# UART.net
KiCad netlist of a schematic drawn in Altium Designer
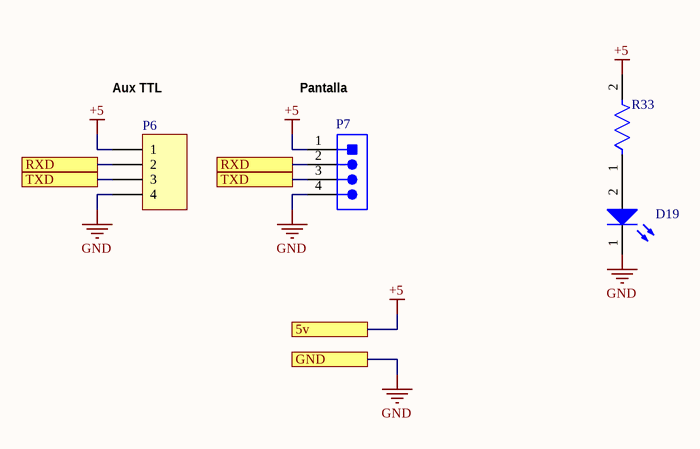
[diagram p0: UART.SchDoc]

(export (version "E")
  (design (tool "Eeschema 10.0.6"))
  (components
    (comp (ref "D19")
      (value "150080BS75000")
      (footprint "WL-SMCW_0805_150080xx75000")
      (libsource (lib "Altium Content Vault") (part "LED_Blue_2A-1K"))
    )
    (comp (ref "P6")
      (value "Header 4")
      (footprint "HDR1X4")
      (description "Header, 4-Pin")
      (fields (field (name "PUBLISHER") "Altium Limited"))
      (libsource (lib "Miscellaneous Connectors") (part "Header 4"))
    )
    (comp (ref "P7")
      (value "B4B-PH-K-S(LF)(SN)")
      (footprint "JST-B4B-PH-K-S_V")
      (fields (field (name "MANUFACTURER") "JST"))
      (libsource (lib "Altium Content Vault") (part "CN-1P-M-R4"))
    )
    (comp (ref "R33")
      (value "ERJ-P06F1001V")
      (footprint "FP-ERJP06-IPC_C")
      (description "RES SMD 1K OHM 1% 1/2W 0805")
      (fields (field (name "TOLERANCE") "1%"))
      (libsource (lib "Altium Content Vault") (part "1029c3af85768c4190bb7ad29bc67b5"))
    )
  )
  (nets
    (net (code "1") (name "+5") (class "Default")
      (node (ref "P6") (pin "1") (pinfunction "1_1") (pintype "passive"))
      (node (ref "P7") (pin "1") (pinfunction "1_1") (pintype "passive"))
      (node (ref "R33") (pin "2") (pinfunction "2_2") (pintype "passive"))
    )
    (net (code "2") (name "/RXD") (class "Default")
      (node (ref "P6") (pin "2") (pinfunction "2_2") (pintype "passive"))
      (node (ref "P7") (pin "2") (pinfunction "2_2") (pintype "passive"))
    )
    (net (code "3") (name "/TXD") (class "Default")
      (node (ref "P6") (pin "3") (pinfunction "3_3") (pintype "passive"))
      (node (ref "P7") (pin "3") (pinfunction "3_3") (pintype "passive"))
    )
    (net (code "4") (name "GND") (class "Default")
      (node (ref "D19") (pin "1") (pinfunction "K_1") (pintype "passive"))
      (node (ref "P6") (pin "4") (pinfunction "4_4") (pintype "passive"))
      (node (ref "P7") (pin "4") (pinfunction "4_4") (pintype "passive"))
    )
    (net (code "5") (name "Net-(D19-A)") (class "Default")
      (node (ref "D19") (pin "2") (pinfunction "A_2") (pintype "passive"))
      (node (ref "R33") (pin "1") (pinfunction "1_1") (pintype "passive"))
    )
  )
)
